# TinyCard.net
KiCad netlist of a schematic drawn in EAGLE
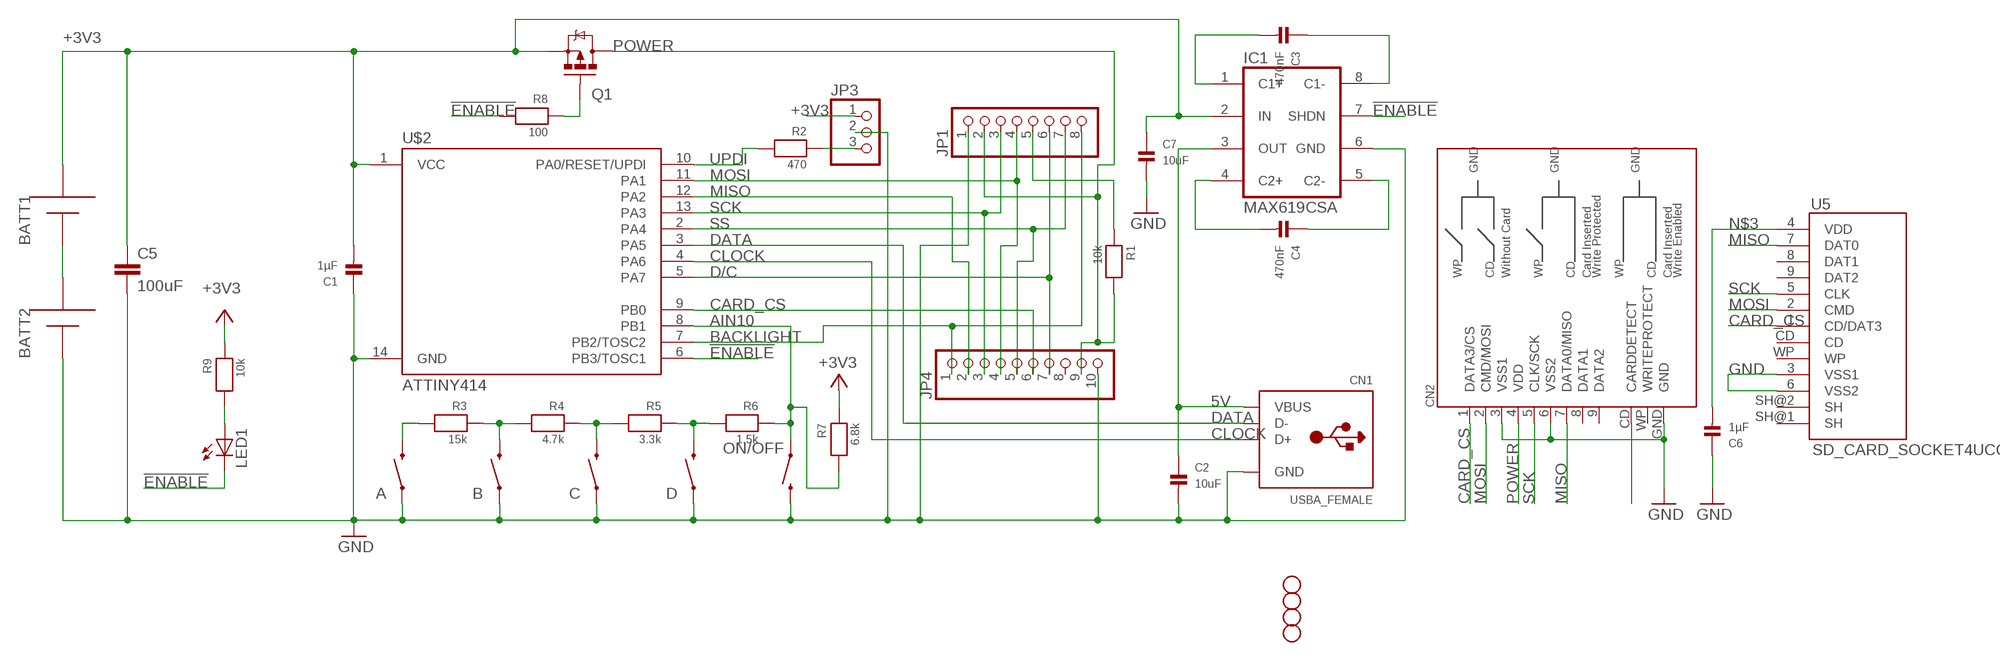
[diagram p0: schematic, sheet 1]

(export (version "E")
  (design (tool "Eeschema 10.0.6"))
  (components
    (comp (ref "A")
      (value "SWITCH-MOMENTARY-212MM")
      (footprint "eagle-import:TACTILE-PTH-12MM")
      (libsource (lib "eagle-import") (part "SWITCH-MOMENTARY-212MM"))
    )
    (comp (ref "B")
      (value "SWITCH-MOMENTARY-212MM")
      (footprint "eagle-import:TACTILE-PTH-12MM")
      (libsource (lib "eagle-import") (part "SWITCH-MOMENTARY-212MM"))
    )
    (comp (ref "BATT1")
      (value "AAA")
      (footprint "eagle-import:12BH412")
      (libsource (lib "eagle-import") (part "AAA"))
    )
    (comp (ref "BATT2")
      (value "AAA")
      (footprint "eagle-import:12BH412")
      (libsource (lib "eagle-import") (part "AAA"))
    )
    (comp (ref "C")
      (value "SWITCH-MOMENTARY-212MM")
      (footprint "eagle-import:TACTILE-PTH-12MM")
      (libsource (lib "eagle-import") (part "SWITCH-MOMENTARY-212MM"))
    )
    (comp (ref "C1")
      (value "1µF")
      (footprint "eagle-import:_0805MP")
      (libsource (lib "eagle-import") (part "CAP_CERAMIC_0805MP"))
    )
    (comp (ref "C2")
      (value "10uF")
      (footprint "eagle-import:_0805MP")
      (libsource (lib "eagle-import") (part "CAP_CERAMIC_0805MP"))
    )
    (comp (ref "C3")
      (value "470nF")
      (footprint "eagle-import:_0805MP")
      (libsource (lib "eagle-import") (part "CAP_CERAMIC_0805MP"))
    )
    (comp (ref "C4")
      (value "470nF")
      (footprint "eagle-import:_0805MP")
      (libsource (lib "eagle-import") (part "CAP_CERAMIC_0805MP"))
    )
    (comp (ref "C5")
      (value "100uF")
      (footprint "eagle-import:1210")
      (libsource (lib "eagle-import") (part "100UF6.3V20%(1210)"))
    )
    (comp (ref "C6")
      (value "1µF")
      (footprint "eagle-import:_0805MP")
      (libsource (lib "eagle-import") (part "CAP_CERAMIC_0805MP"))
    )
    (comp (ref "C7")
      (value "10uF")
      (footprint "eagle-import:_0805MP")
      (libsource (lib "eagle-import") (part "CAP_CERAMIC_0805MP"))
    )
    (comp (ref "CN1")
      (value "USBA_FEMALE")
      (footprint "eagle-import:USB_HOST-PTH")
      (libsource (lib "eagle-import") (part "USB_TYPEAPTHFML"))
    )
    (comp (ref "CN2")
      (value "SDCARD")
      (footprint "eagle-import:SDCARD_SMT_4U06132")
      (libsource (lib "eagle-import") (part "SDCARD"))
    )
    (comp (ref "D")
      (value "SWITCH-MOMENTARY-212MM")
      (footprint "eagle-import:TACTILE-PTH-12MM")
      (libsource (lib "eagle-import") (part "SWITCH-MOMENTARY-212MM"))
    )
    (comp (ref "IC1")
      (value "MAX619CSA")
      (footprint "eagle-import:SO08")
      (fields (field (name "MPN") "MAX634CSA+"))
      (libsource (lib "eagle-import") (part "MAX619CSA"))
    )
    (comp (ref "JP1")
      (value "HEADER-1X8ROUND")
      (footprint "eagle-import:1X08_ROUND")
      (libsource (lib "eagle-import") (part "HEADER-1X8ROUND"))
    )
    (comp (ref "JP3")
      (value "HEADER-1X3ROUND")
      (footprint "eagle-import:1X03_ROUND")
      (libsource (lib "eagle-import") (part "HEADER-1X3ROUND"))
    )
    (comp (ref "JP4")
      (value "HEADER-1X10ROUND")
      (footprint "eagle-import:1X10_ROUND")
      (libsource (lib "eagle-import") (part "HEADER-1X10ROUND"))
    )
    (comp (ref "JP5")
      (value "STAND-OFF")
      (footprint "eagle-import:STAND-OFF")
      (libsource (lib "eagle-import") (part "STAND-OFF"))
    )
    (comp (ref "JP6")
      (value "STAND-OFF")
      (footprint "eagle-import:STAND-OFF")
      (libsource (lib "eagle-import") (part "STAND-OFF"))
    )
    (comp (ref "JP7")
      (value "STAND-OFF")
      (footprint "eagle-import:STAND-OFF")
      (libsource (lib "eagle-import") (part "STAND-OFF"))
    )
    (comp (ref "JP8")
      (value "STAND-OFF")
      (footprint "eagle-import:STAND-OFF")
      (libsource (lib "eagle-import") (part "STAND-OFF"))
    )
    (comp (ref "LED1")
      (value "LEDCHIPLED_0805")
      (footprint "eagle-import:CHIPLED_0805")
      (libsource (lib "eagle-import") (part "LEDCHIPLED_0805"))
    )
    (comp (ref "ON/OFF")
      (value "SWITCH-MOMENTARY-2PTH")
      (footprint "eagle-import:TACTILE-PTH")
      (libsource (lib "eagle-import") (part "SWITCH-MOMENTARY-2PTH"))
    )
    (comp (ref "Q1")
      (value "MOSFET-PCHANNELSMD")
      (footprint "eagle-import:SOT23-3")
      (libsource (lib "eagle-import") (part "MOSFET-PCHANNELSMD"))
    )
    (comp (ref "R1")
      (value "10k")
      (footprint "eagle-import:_0805MP")
      (libsource (lib "eagle-import") (part "RESISTOR_0805MP"))
    )
    (comp (ref "R2")
      (value "470")
      (footprint "eagle-import:_0805MP")
      (libsource (lib "eagle-import") (part "RESISTOR_0805MP"))
    )
    (comp (ref "R3")
      (value "15k")
      (footprint "eagle-import:_0805MP")
      (libsource (lib "eagle-import") (part "RESISTOR_0805MP"))
    )
    (comp (ref "R4")
      (value "4.7k")
      (footprint "eagle-import:_0805MP")
      (libsource (lib "eagle-import") (part "RESISTOR_0805MP"))
    )
    (comp (ref "R5")
      (value "3.3k")
      (footprint "eagle-import:_0805MP")
      (libsource (lib "eagle-import") (part "RESISTOR_0805MP"))
    )
    (comp (ref "R6")
      (value "1.5k")
      (footprint "eagle-import:_0805MP")
      (libsource (lib "eagle-import") (part "RESISTOR_0805MP"))
    )
    (comp (ref "R7")
      (value "6.8k")
      (footprint "eagle-import:_0805MP")
      (libsource (lib "eagle-import") (part "RESISTOR_0805MP"))
    )
    (comp (ref "R8")
      (value "100")
      (footprint "eagle-import:_0805MP")
      (libsource (lib "eagle-import") (part "RESISTOR_0805MP"))
    )
    (comp (ref "R9")
      (value "10k")
      (footprint "eagle-import:_0805MP")
      (libsource (lib "eagle-import") (part "RESISTOR_0805MP"))
    )
    (comp (ref "U$2")
      (value "ATTINY414")
      (footprint "eagle-import:SO14")
      (libsource (lib "eagle-import") (part "ATTINY414"))
    )
    (comp (ref "U5")
      (value "SD_CARD_SOCKET4UCON")
      (footprint "eagle-import:SDCARD_4UCONN")
      (libsource (lib "eagle-import") (part "SD_CARD_SOCKET4UCON"))
    )
  )
  (nets
    (net (code "1") (name "+3V3") (class "Default")
      (node (ref "BATT1") (pin "+") (pinfunction "+_+") (pintype "bidirectional"))
      (node (ref "C1") (pin "2") (pinfunction "P$2_2") (pintype "passive"))
      (node (ref "C5") (pin "1") (pinfunction "1_1") (pintype "passive"))
      (node (ref "C7") (pin "1") (pinfunction "P$1_1") (pintype "passive"))
      (node (ref "IC1") (pin "2") (pinfunction "IN_2") (pintype "input"))
      (node (ref "JP3") (pin "1") (pinfunction "1_1") (pintype "passive"))
      (node (ref "Q1") (pin "2") (pinfunction "S_2") (pintype "passive"))
      (node (ref "R7") (pin "1") (pinfunction "1_1") (pintype "passive"))
      (node (ref "R9") (pin "1") (pinfunction "1_1") (pintype "passive"))
      (node (ref "U$2") (pin "1") (pinfunction "VCC_1") (pintype "bidirectional"))
    )
    (net (code "2") (name "/5V") (class "Default")
      (node (ref "C2") (pin "1") (pinfunction "P$1_1") (pintype "passive"))
      (node (ref "CN1") (pin "VBUS") (pinfunction "VBUS_VBUS") (pintype "power_in"))
      (node (ref "IC1") (pin "3") (pinfunction "OUT_3") (pintype "output"))
    )
    (net (code "3") (name "/AIN10") (class "Default")
      (node (ref "ON/OFF") (pin "1") (pinfunction "1_1") (pintype "passive"))
      (node (ref "R6") (pin "1") (pinfunction "1_1") (pintype "passive"))
      (node (ref "R7") (pin "2") (pinfunction "2_2") (pintype "passive"))
      (node (ref "U$2") (pin "8") (pinfunction "PB1_8") (pintype "bidirectional"))
    )
    (net (code "4") (name "/BACKLIGHT") (class "Default")
      (node (ref "JP1") (pin "8") (pinfunction "8_8") (pintype "passive"))
      (node (ref "JP4") (pin "1") (pinfunction "1_1") (pintype "passive"))
      (node (ref "U$2") (pin "7") (pinfunction "PB2/TOSC2_7") (pintype "bidirectional"))
    )
    (net (code "5") (name "/CARD_CS") (class "Default")
      (node (ref "CN2") (pin "1") (pinfunction "DATA3/CS_1") (pintype "bidirectional"))
      (node (ref "JP4") (pin "6") (pinfunction "6_6") (pintype "passive"))
      (node (ref "U$2") (pin "9") (pinfunction "PB0_9") (pintype "bidirectional"))
      (node (ref "U5") (pin "1") (pinfunction "CD/DAT3_1") (pintype "bidirectional"))
    )
    (net (code "6") (name "/CLOCK") (class "Default")
      (node (ref "CN1") (pin "D+") (pinfunction "D+_D+") (pintype "bidirectional"))
      (node (ref "U$2") (pin "4") (pinfunction "PA6_4") (pintype "bidirectional"))
    )
    (net (code "7") (name "/DATA") (class "Default")
      (node (ref "CN1") (pin "D-") (pinfunction "D-_D-") (pintype "bidirectional"))
      (node (ref "U$2") (pin "3") (pinfunction "PA5_3") (pintype "bidirectional"))
    )
    (net (code "8") (name "/D{slash}C") (class "Default")
      (node (ref "JP1") (pin "6") (pinfunction "6_6") (pintype "passive"))
      (node (ref "JP4") (pin "7") (pinfunction "7_7") (pintype "passive"))
      (node (ref "U$2") (pin "5") (pinfunction "PA7_5") (pintype "bidirectional"))
    )
    (net (code "9") (name "/MISO") (class "Default")
      (node (ref "CN2") (pin "7") (pinfunction "DATA0/MISO_7") (pintype "bidirectional"))
      (node (ref "JP4") (pin "2") (pinfunction "2_2") (pintype "passive"))
      (node (ref "U$2") (pin "12") (pinfunction "PA2_12") (pintype "bidirectional"))
      (node (ref "U5") (pin "7") (pinfunction "DAT0_7") (pintype "bidirectional"))
    )
    (net (code "10") (name "/MOSI") (class "Default")
      (node (ref "CN2") (pin "2") (pinfunction "CMD/MOSI_2") (pintype "bidirectional"))
      (node (ref "JP1") (pin "4") (pinfunction "4_4") (pintype "passive"))
      (node (ref "JP4") (pin "4") (pinfunction "4_4") (pintype "passive"))
      (node (ref "U$2") (pin "11") (pinfunction "PA1_11") (pintype "bidirectional"))
      (node (ref "U5") (pin "2") (pinfunction "CMD_2") (pintype "bidirectional"))
    )
    (net (code "11") (name "/N$3") (class "Default")
      (node (ref "C6") (pin "2") (pinfunction "P$2_2") (pintype "passive"))
      (node (ref "U5") (pin "4") (pinfunction "VDD_4") (pintype "power_in"))
    )
    (net (code "12") (name "/POWER") (class "Default")
      (node (ref "CN2") (pin "4") (pinfunction "VDD_4") (pintype "bidirectional"))
      (node (ref "JP1") (pin "2") (pinfunction "2_2") (pintype "passive"))
      (node (ref "JP4") (pin "9") (pinfunction "9_9") (pintype "passive"))
      (node (ref "Q1") (pin "3") (pinfunction "D_3") (pintype "passive"))
      (node (ref "R1") (pin "2") (pinfunction "2_2") (pintype "passive"))
    )
    (net (code "13") (name "/SCK") (class "Default")
      (node (ref "CN2") (pin "5") (pinfunction "CLK/SCK_5") (pintype "bidirectional"))
      (node (ref "JP1") (pin "3") (pinfunction "3_3") (pintype "passive"))
      (node (ref "JP4") (pin "3") (pinfunction "3_3") (pintype "passive"))
      (node (ref "U$2") (pin "13") (pinfunction "PA3_13") (pintype "bidirectional"))
      (node (ref "U5") (pin "5") (pinfunction "CLK_5") (pintype "bidirectional"))
    )
    (net (code "14") (name "/SS") (class "Default")
      (node (ref "JP1") (pin "7") (pinfunction "7_7") (pintype "passive"))
      (node (ref "JP4") (pin "5") (pinfunction "5_5") (pintype "passive"))
      (node (ref "U$2") (pin "2") (pinfunction "PA4_2") (pintype "bidirectional"))
    )
    (net (code "15") (name "/UPDI") (class "Default")
      (node (ref "R2") (pin "2") (pinfunction "2_2") (pintype "passive"))
      (node (ref "U$2") (pin "10") (pinfunction "PA0/RESET/UPDI_10") (pintype "bidirectional"))
    )
    (net (code "16") (name "/~{ENABLE}") (class "Default")
      (node (ref "IC1") (pin "7") (pinfunction "SHDN_7") (pintype "input"))
      (node (ref "LED1") (pin "C") (pinfunction "C_C") (pintype "passive"))
      (node (ref "R8") (pin "2") (pinfunction "2_2") (pintype "passive"))
      (node (ref "U$2") (pin "6") (pinfunction "PB3/TOSC1_6") (pintype "bidirectional"))
    )
    (net (code "17") (name "GND") (class "Default")
      (node (ref "A") (pin "1") (pinfunction "1_1") (pintype "passive"))
      (node (ref "B") (pin "1") (pinfunction "1_1") (pintype "passive"))
      (node (ref "BATT2") (pin "-") (pinfunction "-_-") (pintype "bidirectional"))
      (node (ref "C") (pin "1") (pinfunction "1_1") (pintype "passive"))
      (node (ref "C1") (pin "1") (pinfunction "P$1_1") (pintype "passive"))
      (node (ref "C2") (pin "2") (pinfunction "P$2_2") (pintype "passive"))
      (node (ref "C5") (pin "2") (pinfunction "2_2") (pintype "passive"))
      (node (ref "C6") (pin "1") (pinfunction "P$1_1") (pintype "passive"))
      (node (ref "C7") (pin "2") (pinfunction "P$2_2") (pintype "passive"))
      (node (ref "CN1") (pin "GND") (pinfunction "GND_GND") (pintype "power_in"))
      (node (ref "CN2") (pin "3") (pinfunction "VSS1_3") (pintype "bidirectional"))
      (node (ref "CN2") (pin "6") (pinfunction "VSS2_6") (pintype "bidirectional"))
      (node (ref "CN2") (pin "GND") (pinfunction "GND_GND") (pintype "bidirectional"))
      (node (ref "D") (pin "1") (pinfunction "1_1") (pintype "passive"))
      (node (ref "IC1") (pin "6") (pinfunction "GND_6") (pintype "power_in"))
      (node (ref "JP1") (pin "1") (pinfunction "1_1") (pintype "passive"))
      (node (ref "JP3") (pin "2") (pinfunction "2_2") (pintype "passive"))
      (node (ref "JP4") (pin "10") (pinfunction "10_10") (pintype "passive"))
      (node (ref "ON/OFF") (pin "3") (pinfunction "2_3") (pintype "passive"))
      (node (ref "U$2") (pin "14") (pinfunction "GND_14") (pintype "bidirectional"))
      (node (ref "U5") (pin "3") (pinfunction "VSS1_3") (pintype "power_in"))
      (node (ref "U5") (pin "6") (pinfunction "VSS2_6") (pintype "power_in"))
    )
    (net (code "18") (name "Net-(A-2)") (class "Default")
      (node (ref "A") (pin "3") (pinfunction "2_3") (pintype "passive"))
      (node (ref "R3") (pin "2") (pinfunction "2_2") (pintype "passive"))
    )
    (net (code "19") (name "Net-(B-2)") (class "Default")
      (node (ref "B") (pin "3") (pinfunction "2_3") (pintype "passive"))
      (node (ref "R3") (pin "1") (pinfunction "1_1") (pintype "passive"))
      (node (ref "R4") (pin "2") (pinfunction "2_2") (pintype "passive"))
    )
    (net (code "20") (name "Net-(BATT1-Pad-)") (class "Default")
      (node (ref "BATT1") (pin "-") (pinfunction "-_-") (pintype "bidirectional"))
      (node (ref "BATT2") (pin "+") (pinfunction "+_+") (pintype "bidirectional"))
    )
    (net (code "21") (name "Net-(C-2)") (class "Default")
      (node (ref "C") (pin "3") (pinfunction "2_3") (pintype "passive"))
      (node (ref "R4") (pin "1") (pinfunction "1_1") (pintype "passive"))
      (node (ref "R5") (pin "2") (pinfunction "2_2") (pintype "passive"))
    )
    (net (code "22") (name "Net-(C3-P$1)") (class "Default")
      (node (ref "C3") (pin "1") (pinfunction "P$1_1") (pintype "passive"))
      (node (ref "IC1") (pin "8") (pinfunction "C1-_8") (pintype "input"))
    )
    (net (code "23") (name "Net-(C3-P$2)") (class "Default")
      (node (ref "C3") (pin "2") (pinfunction "P$2_2") (pintype "passive"))
      (node (ref "IC1") (pin "1") (pinfunction "C1+_1") (pintype "input"))
    )
    (net (code "24") (name "Net-(C4-P$1)") (class "Default")
      (node (ref "C4") (pin "1") (pinfunction "P$1_1") (pintype "passive"))
      (node (ref "IC1") (pin "5") (pinfunction "C2-_5") (pintype "input"))
    )
    (net (code "25") (name "Net-(C4-P$2)") (class "Default")
      (node (ref "C4") (pin "2") (pinfunction "P$2_2") (pintype "passive"))
      (node (ref "IC1") (pin "4") (pinfunction "C2+_4") (pintype "input"))
    )
    (net (code "26") (name "Net-(D-2)") (class "Default")
      (node (ref "D") (pin "3") (pinfunction "2_3") (pintype "passive"))
      (node (ref "R5") (pin "1") (pinfunction "1_1") (pintype "passive"))
      (node (ref "R6") (pin "2") (pinfunction "2_2") (pintype "passive"))
    )
    (net (code "27") (name "Net-(JP1-Pad5)") (class "Default")
      (node (ref "JP1") (pin "5") (pinfunction "5_5") (pintype "passive"))
      (node (ref "R1") (pin "1") (pinfunction "1_1") (pintype "passive"))
    )
    (net (code "28") (name "Net-(JP3-Pad3)") (class "Default")
      (node (ref "JP3") (pin "3") (pinfunction "3_3") (pintype "passive"))
      (node (ref "R2") (pin "1") (pinfunction "1_1") (pintype "passive"))
    )
    (net (code "29") (name "Net-(LED1-PadA)") (class "Default")
      (node (ref "LED1") (pin "A") (pinfunction "A_A") (pintype "passive"))
      (node (ref "R9") (pin "2") (pinfunction "2_2") (pintype "passive"))
    )
    (net (code "30") (name "Net-(Q1-G)") (class "Default")
      (node (ref "Q1") (pin "1") (pinfunction "G_1") (pintype "passive"))
      (node (ref "R8") (pin "1") (pinfunction "1_1") (pintype "passive"))
    )
    (net (code "31") (name "unconnected-(CN2-CARDDETECT-PadCD)") (class "Default")
      (node (ref "CN2") (pin "CD") (pinfunction "CARDDETECT_CD") (pintype "bidirectional"))
    )
    (net (code "32") (name "unconnected-(CN2-DATA1-Pad8)") (class "Default")
      (node (ref "CN2") (pin "8") (pinfunction "DATA1_8") (pintype "bidirectional"))
    )
    (net (code "33") (name "unconnected-(CN2-DATA2-Pad9)") (class "Default")
      (node (ref "CN2") (pin "9") (pinfunction "DATA2_9") (pintype "bidirectional"))
    )
    (net (code "34") (name "unconnected-(CN2-WRITEPROTECT-PadWP)") (class "Default")
      (node (ref "CN2") (pin "WP") (pinfunction "WRITEPROTECT_WP") (pintype "bidirectional"))
    )
    (net (code "35") (name "unconnected-(JP4-Pad8)") (class "Default")
      (node (ref "JP4") (pin "8") (pinfunction "8_8") (pintype "passive"))
    )
    (net (code "36") (name "unconnected-(U5-DAT1-Pad8)") (class "Default")
      (node (ref "U5") (pin "8") (pinfunction "DAT1_8") (pintype "bidirectional"))
    )
    (net (code "37") (name "unconnected-(U5-DAT2-Pad9)") (class "Default")
      (node (ref "U5") (pin "9") (pinfunction "DAT2_9") (pintype "bidirectional"))
    )
    (net (code "38") (name "unconnected-(U5-PadCD)") (class "Default")
      (node (ref "U5") (pin "CD") (pinfunction "CD_CD") (pintype "bidirectional"))
    )
    (net (code "39") (name "unconnected-(U5-PadWP)") (class "Default")
      (node (ref "U5") (pin "WP") (pinfunction "WP_WP") (pintype "bidirectional"))
    )
    (net (code "40") (name "unconnected-(U5-SH-PadSH@1)") (class "Default")
      (node (ref "U5") (pin "SH@1") (pinfunction "SH_SH@1") (pintype "bidirectional"))
    )
    (net (code "41") (name "unconnected-(U5-SH-PadSH@2)") (class "Default")
      (node (ref "U5") (pin "SH@2") (pinfunction "SH_SH@2") (pintype "bidirectional"))
    )
  )
)
